# Connectors.net
KiCad netlist of a schematic drawn in Altium Designer
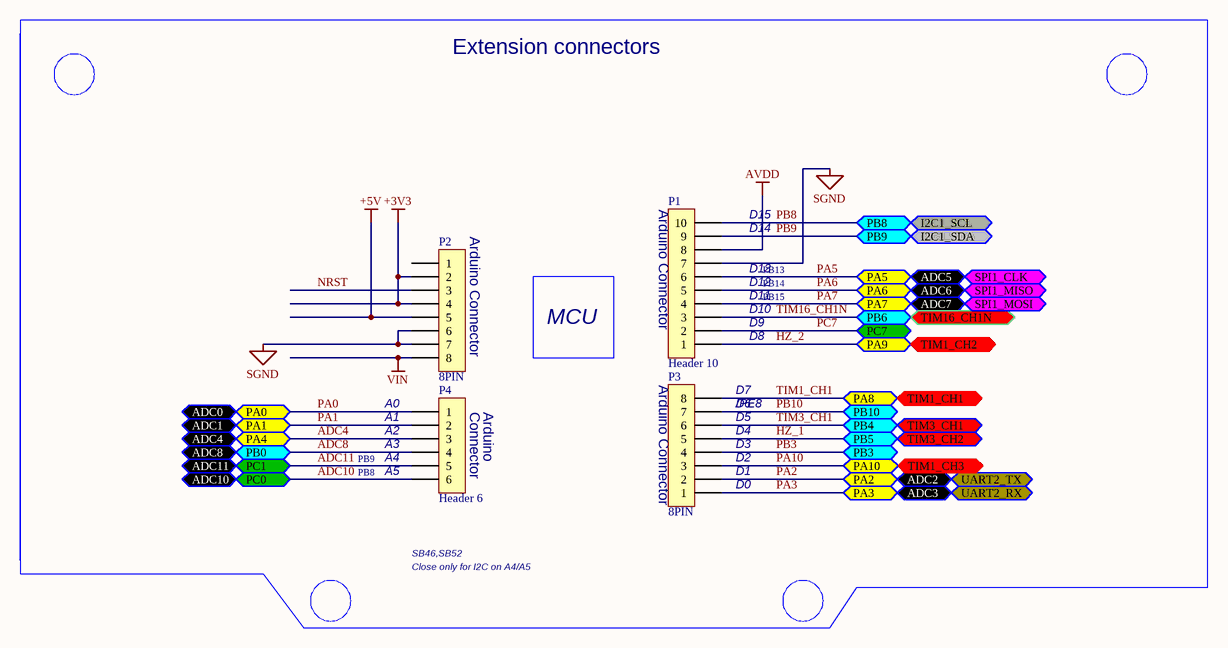
[diagram p0: Connectors.SchDoc]

(export (version "E")
  (design (tool "Eeschema 10.0.6"))
  (components
    (comp (ref "P1")
      (value "Header 10")
      (footprint "CON10-P2.54")
      (description "Header, 10-Pin")
      (fields (field (name "PUBLISHER") "Altium Limited"))
      (libsource (lib "Miscellaneous Connectors") (part "Header 10"))
    )
    (comp (ref "P2")
      (value "8PIN")
      (footprint "CON8-P2.54")
      (description "连接器")
      (fields (field (name "PUBLISHER") "Altium Limited"))
      (libsource (lib "") (part "Header 8_1"))
    )
    (comp (ref "P3")
      (value "8PIN")
      (footprint "CON8-P2.54")
      (description "连接器")
      (fields (field (name "PUBLISHER") "Altium Limited"))
      (libsource (lib "Miscellaneous Connectors") (part "Header 8"))
    )
    (comp (ref "P4")
      (value "Header 6")
      (footprint "CON6-P2.54")
      (description "连接器")
      (fields (field (name "PUBLISHER") "Altium Limited"))
      (libsource (lib "Miscellaneous Connectors") (part "Header 6"))
    )
  )
  (nets
    (net (code "1") (name "+3V3") (class "Default")
      (node (ref "P2") (pin "2") (pinfunction "2_2") (pintype "passive"))
      (node (ref "P2") (pin "4") (pinfunction "4_4") (pintype "passive"))
    )
    (net (code "2") (name "+5V") (class "Default")
      (node (ref "P2") (pin "5") (pinfunction "5_5") (pintype "passive"))
    )
    (net (code "7") (name "/ADC4") (class "Default")
      (node (ref "P4") (pin "3") (pinfunction "3_3") (pintype "passive"))
    )
    (net (code "11") (name "/ADC8") (class "Default")
      (node (ref "P4") (pin "4") (pinfunction "4_4") (pintype "passive"))
    )
    (net (code "12") (name "/ADC10") (class "Default")
      (node (ref "P4") (pin "6") (pinfunction "6_6") (pintype "passive"))
    )
    (net (code "13") (name "/ADC11") (class "Default")
      (node (ref "P4") (pin "5") (pinfunction "5_5") (pintype "passive"))
    )
    (net (code "14") (name "/HZ_1") (class "Default")
      (node (ref "P3") (pin "5") (pinfunction "5_5") (pintype "passive"))
    )
    (net (code "15") (name "/HZ_2") (class "Default")
      (node (ref "P1") (pin "1") (pinfunction "1_1") (pintype "passive"))
    )
    (net (code "18") (name "/NRST") (class "Default")
      (node (ref "P2") (pin "3") (pinfunction "3_3") (pintype "passive"))
    )
    (net (code "19") (name "/PA0") (class "Default")
      (node (ref "P4") (pin "1") (pinfunction "1_1") (pintype "passive"))
    )
    (net (code "20") (name "/PA1") (class "Default")
      (node (ref "P4") (pin "2") (pinfunction "2_2") (pintype "passive"))
    )
    (net (code "21") (name "/PA2") (class "Default")
      (node (ref "P3") (pin "2") (pinfunction "2_2") (pintype "passive"))
    )
    (net (code "22") (name "/PA3") (class "Default")
      (node (ref "P3") (pin "1") (pinfunction "1_1") (pintype "passive"))
    )
    (net (code "23") (name "/PA5") (class "Default")
      (node (ref "P1") (pin "6") (pinfunction "6_6") (pintype "passive"))
    )
    (net (code "24") (name "/PA6") (class "Default")
      (node (ref "P1") (pin "5") (pinfunction "5_5") (pintype "passive"))
    )
    (net (code "25") (name "/PA7") (class "Default")
      (node (ref "P1") (pin "4") (pinfunction "4_4") (pintype "passive"))
    )
    (net (code "26") (name "/PA10") (class "Default")
      (node (ref "P3") (pin "3") (pinfunction "3_3") (pintype "passive"))
    )
    (net (code "27") (name "/PB3") (class "Default")
      (node (ref "P3") (pin "4") (pinfunction "4_4") (pintype "passive"))
    )
    (net (code "28") (name "/PB8") (class "Default")
      (node (ref "P1") (pin "10") (pinfunction "10_10") (pintype "passive"))
    )
    (net (code "29") (name "/PB9") (class "Default")
      (node (ref "P1") (pin "9") (pinfunction "9_9") (pintype "passive"))
    )
    (net (code "30") (name "/PB10") (class "Default")
      (node (ref "P3") (pin "7") (pinfunction "7_7") (pintype "passive"))
    )
    (net (code "31") (name "/PC7") (class "Default")
      (node (ref "P1") (pin "2") (pinfunction "2_2") (pintype "passive"))
    )
    (net (code "35") (name "/TIM1_CH1") (class "Default")
      (node (ref "P3") (pin "8") (pinfunction "8_8") (pintype "passive"))
    )
    (net (code "38") (name "/TIM3_CH1") (class "Default")
      (node (ref "P3") (pin "6") (pinfunction "6_6") (pintype "passive"))
    )
    (net (code "40") (name "/TIM16_CH1N") (class "Default")
      (node (ref "P1") (pin "3") (pinfunction "3_3") (pintype "passive"))
    )
    (net (code "43") (name "AVDD") (class "Default")
      (node (ref "P1") (pin "8") (pinfunction "8_8") (pintype "passive"))
    )
    (net (code "44") (name "SGND") (class "Default")
      (node (ref "P1") (pin "7") (pinfunction "7_7") (pintype "passive"))
      (node (ref "P2") (pin "6") (pinfunction "6_6") (pintype "passive"))
      (node (ref "P2") (pin "7") (pinfunction "7_7") (pintype "passive"))
    )
    (net (code "45") (name "VIN") (class "Default")
      (node (ref "P2") (pin "8") (pinfunction "8_8") (pintype "passive"))
    )
    (net (code "46") (name "unconnected-(P2-Pad1)") (class "Default")
      (node (ref "P2") (pin "1") (pinfunction "1_1") (pintype "passive"))
    )
  )
)
